# Sleep_Timer.net
KiCad netlist of a schematic drawn in Altium Designer
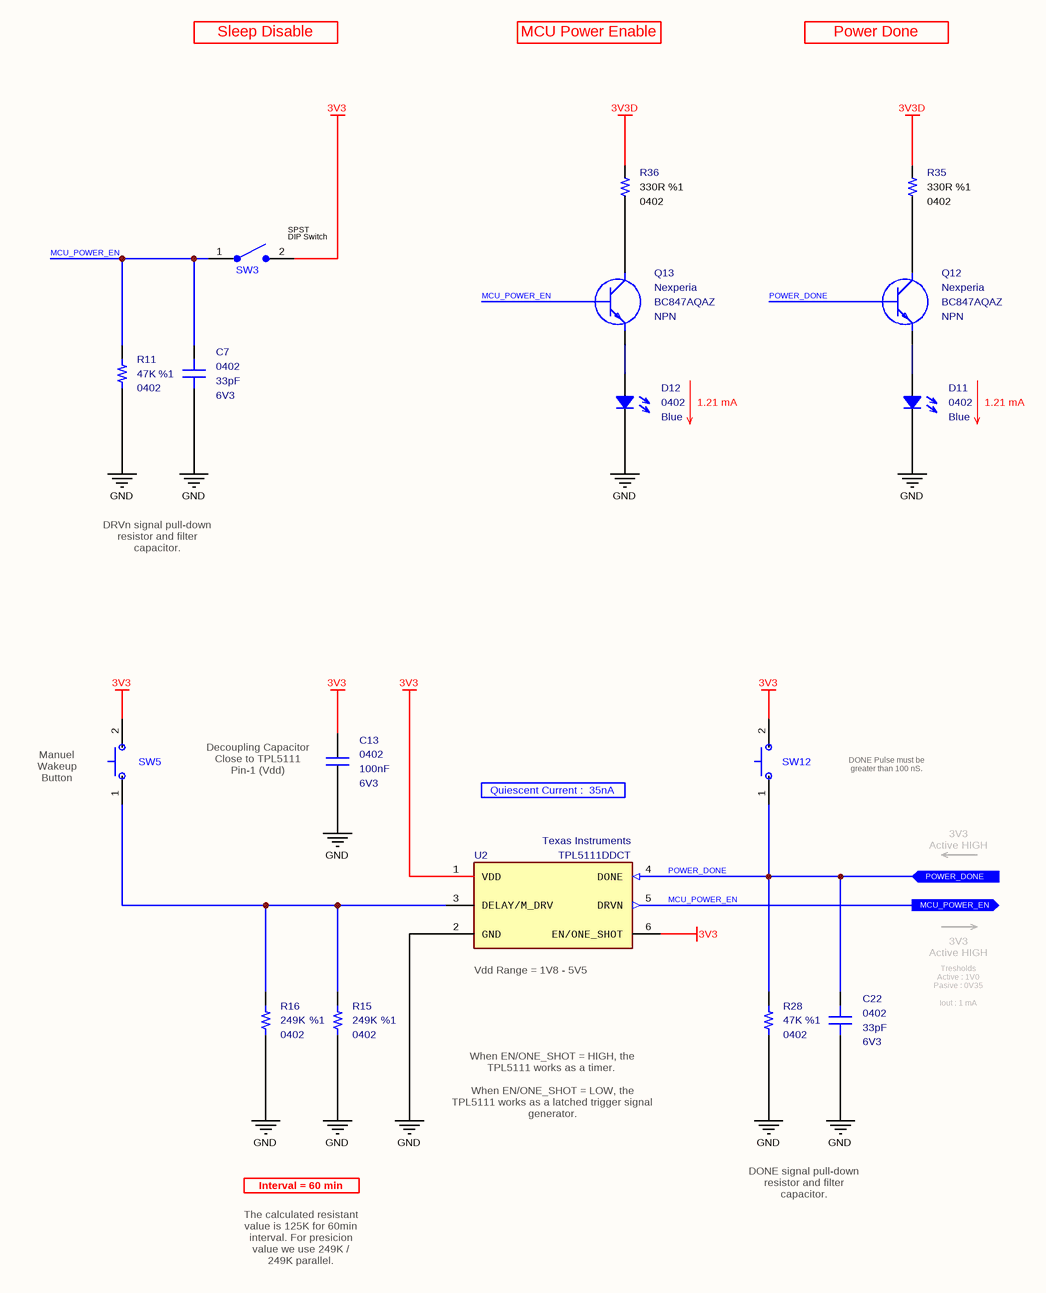
[diagram p0: Sleep Timer.SchDoc]

(export (version "E")
  (design (tool "Eeschema 10.0.6"))
  (components
    (comp (ref "C7")
      (value "33pF")
      (footprint "CAPACITOR_0402")
      (description "Capacitor - 33pF [0402] (Ceramic)")
      (fields
        (field (name "MANUFACTURER_PART_NUMBER") "C0402C330J9RACAUTO")
        (field (name "MOUSER_PART_NUMBER") "80-C0402C330J9RAUTO")
        (field (name "CASE") "0402")
        (field (name "VOLTAGE") "6V3")
      )
      (libsource (lib "Ovoo_Schematic") (part "Capacitor - 33pF [0402-6V3]"))
    )
    (comp (ref "C13")
      (value "100nF")
      (footprint "CAPACITOR_0402")
      (description "Capacitor - 100nF [0402-6V3] (Ceramic)")
      (fields
        (field (name "MANUFACTURER_PART_NUMBER") "04026D104KAT4A")
        (field (name "MOUSER_PART_NUMBER") "581-04026D104KAT4A")
        (field (name "CASE") "0402")
        (field (name "VOLTAGE") "6V3")
      )
      (libsource (lib "Ovoo_Schematic") (part "Capacitor - 100nF [0402-6V3]"))
    )
    (comp (ref "C22")
      (value "33pF")
      (footprint "CAPACITOR_0402")
      (description "Capacitor - 33pF [0402] (Ceramic)")
      (fields
        (field (name "MANUFACTURER_PART_NUMBER") "C0402C330J9RACAUTO")
        (field (name "MOUSER_PART_NUMBER") "80-C0402C330J9RAUTO")
        (field (name "CASE") "0402")
        (field (name "VOLTAGE") "6V3")
      )
      (libsource (lib "Ovoo_Schematic") (part "Capacitor - 33pF [0402-6V3]"))
    )
    (comp (ref "D11")
      (value "SMD LED (Blue)")
      (footprint "LED_0402")
      (description "Standard LEDs - SMD PICOLEDTM;BLUE LED; 25M @ 5MA")
      (fields
        (field (name "MANUFACTURER_PART_NUMBER") "SMLP13BC8TT86")
        (field (name "MOUSER_PART_NUMBER") "755-SMLP13BC8TT86")
        (field (name "CASE") "0402")
        (field (name "COLOR") "Blue")
      )
      (libsource (lib "Ovoo_Library") (part "Diode - LED (0402-Blue)"))
    )
    (comp (ref "D12")
      (value "SMD LED (Blue)")
      (footprint "LED_0402")
      (description "Standard LEDs - SMD PICOLEDTM;BLUE LED; 25M @ 5MA")
      (fields
        (field (name "MANUFACTURER_PART_NUMBER") "SMLP13BC8TT86")
        (field (name "MOUSER_PART_NUMBER") "755-SMLP13BC8TT86")
        (field (name "CASE") "0402")
        (field (name "COLOR") "Blue")
      )
      (libsource (lib "Ovoo_Library") (part "Diode - LED (0402-Blue)"))
    )
    (comp (ref "Q12")
      (value "Bipolar NPN Transistors")
      (footprint "SOT1215")
      (description "Bipolar Transistors - BJT BC847AQA/DFN1010D-3/REEL 7\" Q2")
      (fields
        (field (name "MOUSER_PART_NUMBER") "771-BC847AQAZ")
        (field (name "MANUFACTURER_NAME") "Nexperia")
        (field (name "MANUFACTURER_PART_NUMBER") "BC847AQAZ")
        (field (name "POLARITY") "NPN")
      )
      (libsource (lib "Ovoo_Library") (part "Transistor - BC847"))
    )
    (comp (ref "Q13")
      (value "Bipolar NPN Transistors")
      (footprint "SOT1215")
      (description "Bipolar Transistors - BJT BC847AQA/DFN1010D-3/REEL 7\" Q2")
      (fields
        (field (name "MOUSER_PART_NUMBER") "771-BC847AQAZ")
        (field (name "MANUFACTURER_NAME") "Nexperia")
        (field (name "MANUFACTURER_PART_NUMBER") "BC847AQAZ")
        (field (name "POLARITY") "NPN")
      )
      (libsource (lib "Ovoo_Library") (part "Transistor - BC847"))
    )
    (comp (ref "R11")
      (value "47K")
      (footprint "RESISTOR_0402")
      (description "Thick Film Resistors - SMD 1/16 W 47 Kohms 1%")
      (fields
        (field (name "MANUFACTURER_PART_NUMBER") "CRCW040247K0FKED")
        (field (name "MOUSER_PART_NUMBER") "71-CRCW0402-47K-E3")
        (field (name "TOLERANCE") "%1")
        (field (name "CASE") "0402")
      )
      (libsource (lib "Ovoo_Schematic") (part "Resistor - 47K"))
    )
    (comp (ref "R15")
      (value "249K")
      (footprint "RESISTOR_0402")
      (description "Thick Film Resistors - SMD 1/16 W 249 Kohms 1%")
      (fields
        (field (name "MANUFACTURER_PART_NUMBER") "CRCW0402249KFKED")
        (field (name "MOUSER_PART_NUMBER") "71-CRCW0402-249K-E3")
        (field (name "TOLERANCE") "%1")
        (field (name "CASE") "0402")
      )
      (libsource (lib "Ovoo_Schematic") (part "Resistor - 249K"))
    )
    (comp (ref "R16")
      (value "249K")
      (footprint "RESISTOR_0402")
      (description "Thick Film Resistors - SMD 1/16 W 249 Kohms 1%")
      (fields
        (field (name "MANUFACTURER_PART_NUMBER") "CRCW0402249KFKED")
        (field (name "MOUSER_PART_NUMBER") "71-CRCW0402-249K-E3")
        (field (name "TOLERANCE") "%1")
        (field (name "CASE") "0402")
      )
      (libsource (lib "Ovoo_Schematic") (part "Resistor - 249K"))
    )
    (comp (ref "R28")
      (value "47K")
      (footprint "RESISTOR_0402")
      (description "Thick Film Resistors - SMD 1/16 W 47 Kohms 1%")
      (fields
        (field (name "MANUFACTURER_PART_NUMBER") "CRCW040247K0FKED")
        (field (name "MOUSER_PART_NUMBER") "71-CRCW0402-47K-E3")
        (field (name "TOLERANCE") "%1")
        (field (name "CASE") "0402")
      )
      (libsource (lib "Ovoo_Schematic") (part "Resistor - 47K"))
    )
    (comp (ref "R35")
      (value "330R")
      (footprint "RESISTOR_0402")
      (description "Thick Film Resistors - SMD 1/16 W 330 Ohm 1%")
      (fields
        (field (name "TOLERANCE") "%1")
        (field (name "CASE") "0402")
        (field (name "MANUFACTURER PART NUMBER") "CRCW0402330RFKED")
        (field (name "MOUSER PART NUMBER") "71-CRCW0402-330-E3")
      )
      (libsource (lib "Ovoo_Library") (part "Resistor - 330R"))
    )
    (comp (ref "R36")
      (value "330R")
      (footprint "RESISTOR_0402")
      (description "Thick Film Resistors - SMD 1/16 W 330 Ohm 1%")
      (fields
        (field (name "TOLERANCE") "%1")
        (field (name "CASE") "0402")
        (field (name "MANUFACTURER PART NUMBER") "CRCW0402330RFKED")
        (field (name "MOUSER PART NUMBER") "71-CRCW0402-330-E3")
      )
      (libsource (lib "Ovoo_Library") (part "Resistor - 330R"))
    )
    (comp (ref "SW3")
      (value "DIP Switch")
      (footprint "DS04-254-2-01BK-SMT-TR")
      (fields
        (field (name "MANUFACTURER PART NUMBER") "DS04-254-2-01BK-SMT-TR")
        (field (name "MOUSER PART NUMBER") "490-DS04254201BK-STR")
      )
      (libsource (lib "Ovoo_Library") (part "Switch - DIP Switch (1 Pole)"))
    )
    (comp (ref "SW5")
      (value "Tactile Switches")
      (footprint "PTS526_Switch")
      (description "Tactile Switches 50mA 12VDC, 5.2x5.2mm, 0.8mm H, 260gf, G leads.")
      (fields
        (field (name "MANUFACTURER PART NUMBER") "PTS526 SK08 SMTR2 LFS")
        (field (name "MOUSER PART NUMBER") "611-PTS526SK08SMTR2L")
      )
      (libsource (lib "Ovoo_Library") (part "Switch - Tactile"))
    )
    (comp (ref "SW12")
      (value "Tactile Switches")
      (footprint "PTS526_Switch")
      (description "Tactile Switches 50mA 12VDC, 5.2x5.2mm, 0.8mm H, 260gf, G leads.")
      (fields
        (field (name "MANUFACTURER PART NUMBER") "PTS526 SK08 SMTR2 LFS")
        (field (name "MOUSER PART NUMBER") "611-PTS526SK08SMTR2L")
      )
      (libsource (lib "Ovoo_Library") (part "Switch - Tactile"))
    )
    (comp (ref "U2")
      (value "Nanopower Timer IC")
      (footprint "SOT-23-6")
      (fields
        (field (name "MOUSER_PART_NUMBER") "595-TPL5111DDCT")
        (field (name "MANUFACTURER _PART_NUMBER") "TPL5111DDCT")
        (field (name "MANUFACTURER_NAME") "Texas Instruments")
      )
      (libsource (lib "Ovoo_Schematic") (part "IC - TPL5111"))
    )
  )
  (nets
    (net (code "1") (name "/MCU_POWER_EN") (class "Default")
      (node (ref "C7") (pin "2") (pinfunction "2_2") (pintype "passive"))
      (node (ref "Q13") (pin "1") (pinfunction "B_1") (pintype "passive"))
      (node (ref "R11") (pin "2") (pinfunction "2_2") (pintype "passive"))
      (node (ref "SW3") (pin "1") (pinfunction "COM_1") (pintype "passive"))
      (node (ref "U2") (pin "5") (pinfunction "DRVN_5") (pintype "output"))
    )
    (net (code "2") (name "/POWER_DONE") (class "Default")
      (node (ref "C22") (pin "2") (pinfunction "2_2") (pintype "passive"))
      (node (ref "Q12") (pin "1") (pinfunction "B_1") (pintype "passive"))
      (node (ref "R28") (pin "2") (pinfunction "2_2") (pintype "passive"))
      (node (ref "SW12") (pin "1") (pinfunction "NC_1") (pintype "passive"))
      (node (ref "U2") (pin "4") (pinfunction "DONE_4") (pintype "input"))
    )
    (net (code "3") (name "3V3") (class "Default")
      (node (ref "C13") (pin "2") (pinfunction "2_2") (pintype "passive"))
      (node (ref "SW12") (pin "2") (pinfunction "COM_2") (pintype "passive"))
      (node (ref "SW3") (pin "2") (pinfunction "NO_2") (pintype "passive"))
      (node (ref "SW5") (pin "2") (pinfunction "COM_2") (pintype "passive"))
      (node (ref "U2") (pin "1") (pinfunction "VDD_1") (pintype "power_in"))
      (node (ref "U2") (pin "6") (pinfunction "EN/ONE_SHOT_6") (pintype "passive"))
    )
    (net (code "4") (name "3V3D") (class "Default")
      (node (ref "R35") (pin "2") (pinfunction "2_2") (pintype "passive"))
      (node (ref "R36") (pin "2") (pinfunction "2_2") (pintype "passive"))
    )
    (net (code "5") (name "GND") (class "Default")
      (node (ref "C13") (pin "1") (pinfunction "1_1") (pintype "passive"))
      (node (ref "C22") (pin "1") (pinfunction "1_1") (pintype "passive"))
      (node (ref "C7") (pin "1") (pinfunction "1_1") (pintype "passive"))
      (node (ref "D11") (pin "1") (pinfunction "1_1") (pintype "passive"))
      (node (ref "D12") (pin "1") (pinfunction "1_1") (pintype "passive"))
      (node (ref "R11") (pin "1") (pinfunction "1_1") (pintype "passive"))
      (node (ref "R15") (pin "1") (pinfunction "1_1") (pintype "passive"))
      (node (ref "R16") (pin "1") (pinfunction "1_1") (pintype "passive"))
      (node (ref "R28") (pin "1") (pinfunction "1_1") (pintype "passive"))
      (node (ref "U2") (pin "2") (pinfunction "GND_2") (pintype "power_in"))
    )
    (net (code "6") (name "Net-(Q12-C)") (class "Default")
      (node (ref "Q12") (pin "3") (pinfunction "C_3") (pintype "passive"))
      (node (ref "R35") (pin "1") (pinfunction "1_1") (pintype "passive"))
    )
    (net (code "7") (name "Net-(Q12-E)") (class "Default")
      (node (ref "D11") (pin "2") (pinfunction "2_2") (pintype "passive"))
      (node (ref "Q12") (pin "2") (pinfunction "E_2") (pintype "passive"))
    )
    (net (code "8") (name "Net-(Q13-C)") (class "Default")
      (node (ref "Q13") (pin "3") (pinfunction "C_3") (pintype "passive"))
      (node (ref "R36") (pin "1") (pinfunction "1_1") (pintype "passive"))
    )
    (net (code "9") (name "Net-(Q13-E)") (class "Default")
      (node (ref "D12") (pin "2") (pinfunction "2_2") (pintype "passive"))
      (node (ref "Q13") (pin "2") (pinfunction "E_2") (pintype "passive"))
    )
    (net (code "10") (name "Net-(SW5-NC)") (class "Default")
      (node (ref "R15") (pin "2") (pinfunction "2_2") (pintype "passive"))
      (node (ref "R16") (pin "2") (pinfunction "2_2") (pintype "passive"))
      (node (ref "SW5") (pin "1") (pinfunction "NC_1") (pintype "passive"))
      (node (ref "U2") (pin "3") (pinfunction "DELAY/M_DRV_3") (pintype "passive"))
    )
  )
)
